# LilyTiny.net
KiCad netlist of a schematic drawn in EAGLE
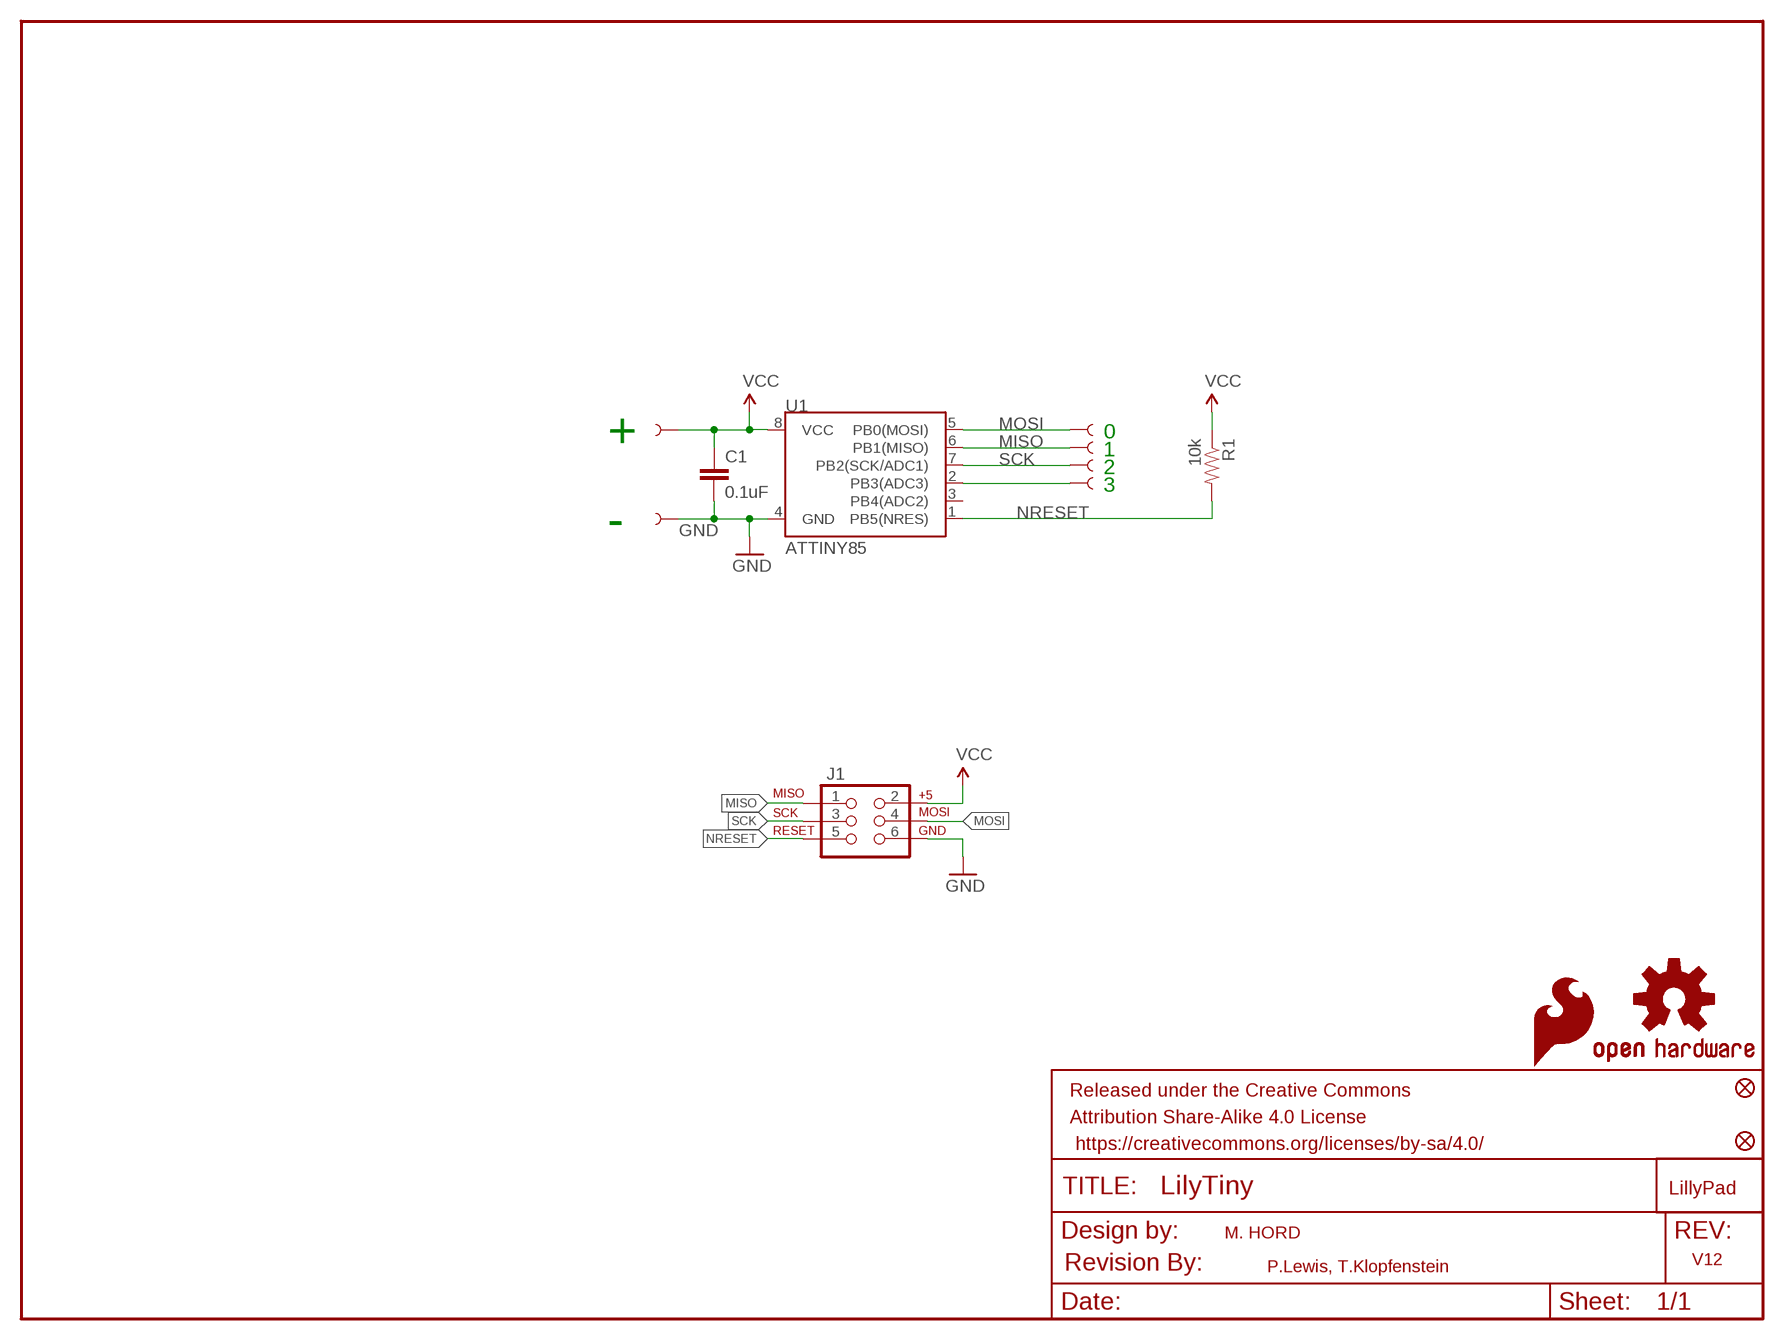
[diagram p0: schematic, sheet 1]

(export (version "E")
  (design (tool "Eeschema 10.0.6"))
  (components
    (comp (ref "C1")
      (value "0.1uF")
      (footprint "eagle-import:0603-CAP")
      (libsource (lib "eagle-import") (part "CAP0603-CAP"))
    )
    (comp (ref "FID1")
      (value "FIDUCIAL1X2")
      (footprint "eagle-import:FIDUCIAL-1X2")
      (libsource (lib "eagle-import") (part "FIDUCIAL1X2"))
    )
    (comp (ref "FID2")
      (value "FIDUCIAL1X2")
      (footprint "eagle-import:FIDUCIAL-1X2")
      (libsource (lib "eagle-import") (part "FIDUCIAL1X2"))
    )
    (comp (ref "FRAME2")
      (value "FRAME-LETTER")
      (footprint "eagle-import:CREATIVE_COMMONS")
      (libsource (lib "eagle-import") (part "FRAME-LETTER"))
    )
    (comp (ref "J1")
      (value "AVR_SPI_PRG_6TESTPOINTS")
      (footprint "eagle-import:2X3_TEST_POINTS")
      (libsource (lib "eagle-import") (part "AVR_SPI_PRG_6TESTPOINTS"))
    )
    (comp (ref "LOGO1")
      (value "OSHW-LOGOS")
      (footprint "eagle-import:OSHW-LOGO-S")
      (libsource (lib "eagle-import") (part "OSHW-LOGOS"))
    )
    (comp (ref "LOGO2")
      (value "SFE_LOGO_FLAME.1_INCH")
      (footprint "eagle-import:SFE_LOGO_FLAME_.1")
      (libsource (lib "eagle-import") (part "SFE_LOGO_FLAME.1_INCH"))
    )
    (comp (ref "R1")
      (value "10k")
      (footprint "eagle-import:0603-RES")
      (libsource (lib "eagle-import") (part "RESISTOR0603-RES"))
    )
    (comp (ref "U$1")
      (value "REVISION")
      (footprint "eagle-import:REVISION")
      (libsource (lib "eagle-import") (part "REVISION"))
    )
    (comp (ref "U$2")
      (value "SEWTAP6")
      (footprint "eagle-import:PETAL-SMALL-2SIDE")
      (libsource (lib "eagle-import") (part "SEWTAP6"))
    )
    (comp (ref "U$3")
      (value "SEWTAP6")
      (footprint "eagle-import:PETAL-SMALL-2SIDE")
      (libsource (lib "eagle-import") (part "SEWTAP6"))
    )
    (comp (ref "U$4")
      (value "SEWTAP6")
      (footprint "eagle-import:PETAL-SMALL-2SIDE")
      (libsource (lib "eagle-import") (part "SEWTAP6"))
    )
    (comp (ref "U$5")
      (value "SEWTAP6")
      (footprint "eagle-import:PETAL-SMALL-2SIDE")
      (libsource (lib "eagle-import") (part "SEWTAP6"))
    )
    (comp (ref "U$6")
      (value "SEWTAP6")
      (footprint "eagle-import:PETAL-SMALL-2SIDE")
      (libsource (lib "eagle-import") (part "SEWTAP6"))
    )
    (comp (ref "U$7")
      (value "SEWTAP6")
      (footprint "eagle-import:PETAL-SMALL-2SIDE")
      (libsource (lib "eagle-import") (part "SEWTAP6"))
    )
    (comp (ref "U$8")
      (value "LOGO-LPL")
      (footprint "eagle-import:LOGO-L")
      (libsource (lib "eagle-import") (part "LOGO-LPL"))
    )
    (comp (ref "U1")
      (value "ATTINY85")
      (footprint "eagle-import:SO08-EIAJ")
      (libsource (lib "eagle-import") (part "ATTINY45"))
    )
  )
  (nets
    (net (code "1") (name "GND") (class "Default")
      (node (ref "C1") (pin "2") (pinfunction "2_2") (pintype "passive"))
      (node (ref "J1") (pin "6") (pinfunction "6_6") (pintype "passive"))
      (node (ref "U$2") (pin "1") (pinfunction "1_1") (pintype "bidirectional"))
      (node (ref "U1") (pin "4") (pinfunction "GND_4") (pintype "bidirectional"))
    )
    (net (code "2") (name "MISO") (class "Default")
      (node (ref "J1") (pin "1") (pinfunction "1_1") (pintype "passive"))
      (node (ref "U$3") (pin "1") (pinfunction "1_1") (pintype "bidirectional"))
      (node (ref "U1") (pin "6") (pinfunction "PB1(MISO)_6") (pintype "bidirectional"))
    )
    (net (code "3") (name "MOSI") (class "Default")
      (node (ref "J1") (pin "4") (pinfunction "4_4") (pintype "passive"))
      (node (ref "U$7") (pin "1") (pinfunction "1_1") (pintype "bidirectional"))
      (node (ref "U1") (pin "5") (pinfunction "PB0(MOSI)_5") (pintype "bidirectional"))
    )
    (net (code "4") (name "NRESET") (class "Default")
      (node (ref "J1") (pin "5") (pinfunction "5_5") (pintype "passive"))
      (node (ref "R1") (pin "2") (pinfunction "2_2") (pintype "passive"))
      (node (ref "U1") (pin "1") (pinfunction "PB5(NRES)_1") (pintype "bidirectional"))
    )
    (net (code "5") (name "Net-(U1-PB3(ADC3))") (class "Default")
      (node (ref "U$6") (pin "1") (pinfunction "1_1") (pintype "bidirectional"))
      (node (ref "U1") (pin "2") (pinfunction "PB3(ADC3)_2") (pintype "bidirectional"))
    )
    (net (code "6") (name "SCK") (class "Default")
      (node (ref "J1") (pin "3") (pinfunction "3_3") (pintype "passive"))
      (node (ref "U$4") (pin "1") (pinfunction "1_1") (pintype "bidirectional"))
      (node (ref "U1") (pin "7") (pinfunction "PB2(SCK/ADC1)_7") (pintype "bidirectional"))
    )
    (net (code "7") (name "VCC") (class "Default")
      (node (ref "C1") (pin "1") (pinfunction "1_1") (pintype "passive"))
      (node (ref "J1") (pin "2") (pinfunction "2_2") (pintype "passive"))
      (node (ref "R1") (pin "1") (pinfunction "1_1") (pintype "passive"))
      (node (ref "U$5") (pin "1") (pinfunction "1_1") (pintype "bidirectional"))
      (node (ref "U1") (pin "8") (pinfunction "VCC_8") (pintype "bidirectional"))
    )
    (net (code "8") (name "unconnected-(U1-PB4(ADC2)-Pad3)") (class "Default")
      (node (ref "U1") (pin "3") (pinfunction "PB4(ADC2)_3") (pintype "bidirectional"))
    )
  )
)
